# FreedomWing.net
KiCad netlist of a schematic drawn in EAGLE
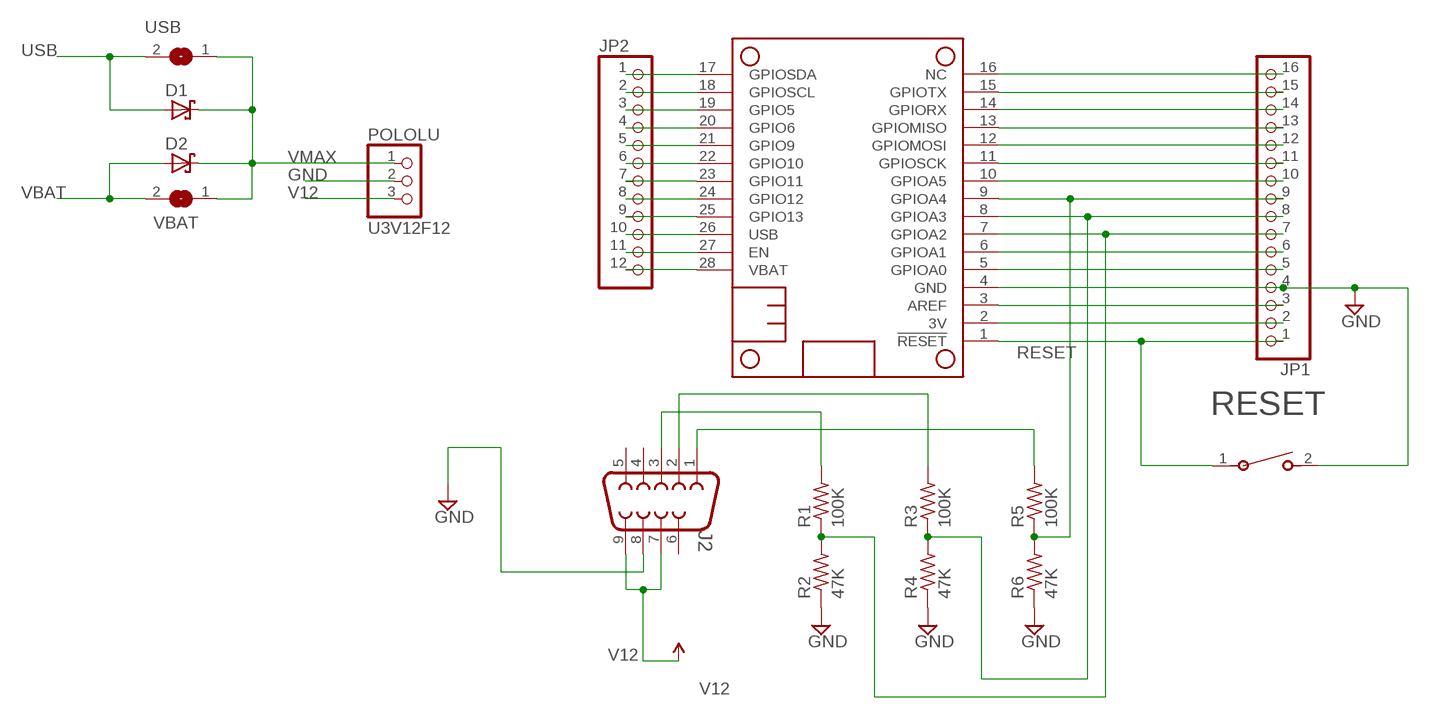
[diagram p0: schematic, sheet 1]

(export (version "E")
  (design (tool "Eeschema 10.0.6"))
  (components
    (comp (ref "D1")
      (value "SCHOTTKY-DIODEDO41-7")
      (footprint "eagle-import:DO41-7")
      (libsource (lib "eagle-import") (part "SCHOTTKY-DIODEDO41-7"))
    )
    (comp (ref "D2")
      (value "SCHOTTKY-DIODEDO41-7")
      (footprint "eagle-import:DO41-7")
      (libsource (lib "eagle-import") (part "SCHOTTKY-DIODEDO41-7"))
    )
    (comp (ref "J2")
      (value "DB9MALE")
      (footprint "eagle-import:DB9_MALE")
      (libsource (lib "eagle-import") (part "DB9MALE"))
    )
    (comp (ref "JP1")
      (value "PINHD-1X16")
      (footprint "eagle-import:1X16")
      (libsource (lib "eagle-import") (part "PINHD-1X16"))
    )
    (comp (ref "JP2")
      (value "PINHD-1X12")
      (footprint "eagle-import:1X12")
      (libsource (lib "eagle-import") (part "PINHD-1X12"))
    )
    (comp (ref "MS1")
      (value "FEATHERWING_NODIM")
      (footprint "eagle-import:FEATHERWING_DIM")
      (libsource (lib "eagle-import") (part "FEATHERWING_NODIM"))
    )
    (comp (ref "POLOLU")
      (value "U3V12F12")
      (footprint "eagle-import:1X03")
      (libsource (lib "eagle-import") (part "PINHD-1X3"))
    )
    (comp (ref "R1")
      (value "100K")
      (footprint "eagle-import:0207_10")
      (libsource (lib "eagle-import") (part "R-US_0207/10"))
    )
    (comp (ref "R2")
      (value "47K")
      (footprint "eagle-import:0207_10")
      (libsource (lib "eagle-import") (part "R-US_0207/10"))
    )
    (comp (ref "R3")
      (value "100K")
      (footprint "eagle-import:0207_10")
      (libsource (lib "eagle-import") (part "R-US_0207/10"))
    )
    (comp (ref "R4")
      (value "47K")
      (footprint "eagle-import:0207_10")
      (libsource (lib "eagle-import") (part "R-US_0207/10"))
    )
    (comp (ref "R5")
      (value "100K")
      (footprint "eagle-import:0207_10")
      (libsource (lib "eagle-import") (part "R-US_0207/10"))
    )
    (comp (ref "R6")
      (value "47K")
      (footprint "eagle-import:0207_10")
      (libsource (lib "eagle-import") (part "R-US_0207/10"))
    )
    (comp (ref "RESET")
      (value "1825966-1")
      (footprint "eagle-import:SWDIP2_256X170P100")
      (fields (field (name "COPYRIGHT") "Copyright (C) 2016 Accelerated Designs. All rights reserved"))
      (libsource (lib "eagle-import") (part "1825966-1"))
    )
    (comp (ref "USB")
      (value "SJW")
      (footprint "eagle-import:SJW")
      (libsource (lib "eagle-import") (part "SJW"))
    )
    (comp (ref "VBAT")
      (value "SJW")
      (footprint "eagle-import:SJW")
      (libsource (lib "eagle-import") (part "SJW"))
    )
  )
  (nets
    (net (code "1") (name "/RESET") (class "Default")
      (node (ref "JP1") (pin "1") (pinfunction "1_1") (pintype "passive"))
      (node (ref "MS1") (pin "1") (pinfunction "~{RESET}_1") (pintype "input"))
      (node (ref "RESET") (pin "1") (pinfunction "1_1") (pintype "passive"))
    )
    (net (code "2") (name "/USB") (class "Default")
      (node (ref "D1") (pin "A") (pinfunction "A_A") (pintype "passive"))
      (node (ref "JP2") (pin "10") (pinfunction "10_10") (pintype "passive"))
      (node (ref "MS1") (pin "26") (pinfunction "USB_26") (pintype "power_in"))
      (node (ref "USB") (pin "2") (pinfunction "2_2") (pintype "passive"))
    )
    (net (code "3") (name "/VBAT") (class "Default")
      (node (ref "D2") (pin "A") (pinfunction "A_A") (pintype "passive"))
      (node (ref "JP2") (pin "12") (pinfunction "12_12") (pintype "passive"))
      (node (ref "MS1") (pin "28") (pinfunction "VBAT_28") (pintype "power_in"))
      (node (ref "VBAT") (pin "2") (pinfunction "2_2") (pintype "passive"))
    )
    (net (code "4") (name "/VMAX") (class "Default")
      (node (ref "D1") (pin "C") (pinfunction "C_C") (pintype "passive"))
      (node (ref "D2") (pin "C") (pinfunction "C_C") (pintype "passive"))
      (node (ref "POLOLU") (pin "1") (pinfunction "1_1") (pintype "passive"))
      (node (ref "USB") (pin "1") (pinfunction "1_1") (pintype "passive"))
      (node (ref "VBAT") (pin "1") (pinfunction "1_1") (pintype "passive"))
    )
    (net (code "5") (name "GND") (class "Default")
      (node (ref "J2") (pin "8") (pinfunction "8_8") (pintype "passive"))
      (node (ref "JP1") (pin "4") (pinfunction "4_4") (pintype "passive"))
      (node (ref "MS1") (pin "4") (pinfunction "GND_4") (pintype "power_in"))
      (node (ref "POLOLU") (pin "2") (pinfunction "2_2") (pintype "passive"))
      (node (ref "R2") (pin "1") (pinfunction "1_1") (pintype "passive"))
      (node (ref "R4") (pin "1") (pinfunction "1_1") (pintype "passive"))
      (node (ref "R6") (pin "1") (pinfunction "1_1") (pintype "passive"))
      (node (ref "RESET") (pin "2") (pinfunction "2_2") (pintype "passive"))
    )
    (net (code "6") (name "Net-(J2-Pad1)") (class "Default")
      (node (ref "J2") (pin "1") (pinfunction "1_1") (pintype "passive"))
      (node (ref "R5") (pin "2") (pinfunction "2_2") (pintype "passive"))
    )
    (net (code "7") (name "Net-(J2-Pad2)") (class "Default")
      (node (ref "J2") (pin "2") (pinfunction "2_2") (pintype "passive"))
      (node (ref "R3") (pin "2") (pinfunction "2_2") (pintype "passive"))
    )
    (net (code "8") (name "Net-(J2-Pad3)") (class "Default")
      (node (ref "J2") (pin "3") (pinfunction "3_3") (pintype "passive"))
      (node (ref "R1") (pin "2") (pinfunction "2_2") (pintype "passive"))
    )
    (net (code "9") (name "Net-(MS1-3V)") (class "Default")
      (node (ref "JP1") (pin "2") (pinfunction "2_2") (pintype "passive"))
      (node (ref "MS1") (pin "2") (pinfunction "3V_2") (pintype "power_in"))
    )
    (net (code "10") (name "Net-(MS1-AREF)") (class "Default")
      (node (ref "JP1") (pin "3") (pinfunction "3_3") (pintype "passive"))
      (node (ref "MS1") (pin "3") (pinfunction "AREF_3") (pintype "passive"))
    )
    (net (code "11") (name "Net-(MS1-EN)") (class "Default")
      (node (ref "JP2") (pin "11") (pinfunction "11_11") (pintype "passive"))
      (node (ref "MS1") (pin "27") (pinfunction "EN_27") (pintype "passive"))
    )
    (net (code "12") (name "Net-(MS1-GPIO5)") (class "Default")
      (node (ref "JP2") (pin "3") (pinfunction "3_3") (pintype "passive"))
      (node (ref "MS1") (pin "19") (pinfunction "GPIO5_19") (pintype "bidirectional"))
    )
    (net (code "13") (name "Net-(MS1-GPIO6)") (class "Default")
      (node (ref "JP2") (pin "4") (pinfunction "4_4") (pintype "passive"))
      (node (ref "MS1") (pin "20") (pinfunction "GPIO6_20") (pintype "bidirectional"))
    )
    (net (code "14") (name "Net-(MS1-GPIO9)") (class "Default")
      (node (ref "JP2") (pin "5") (pinfunction "5_5") (pintype "passive"))
      (node (ref "MS1") (pin "21") (pinfunction "GPIO9_21") (pintype "bidirectional"))
    )
    (net (code "15") (name "Net-(MS1-GPIO10)") (class "Default")
      (node (ref "JP2") (pin "6") (pinfunction "6_6") (pintype "passive"))
      (node (ref "MS1") (pin "22") (pinfunction "GPIO10_22") (pintype "bidirectional"))
    )
    (net (code "16") (name "Net-(MS1-GPIO11)") (class "Default")
      (node (ref "JP2") (pin "7") (pinfunction "7_7") (pintype "passive"))
      (node (ref "MS1") (pin "23") (pinfunction "GPIO11_23") (pintype "bidirectional"))
    )
    (net (code "17") (name "Net-(MS1-GPIO12)") (class "Default")
      (node (ref "JP2") (pin "8") (pinfunction "8_8") (pintype "passive"))
      (node (ref "MS1") (pin "24") (pinfunction "GPIO12_24") (pintype "bidirectional"))
    )
    (net (code "18") (name "Net-(MS1-GPIO13)") (class "Default")
      (node (ref "JP2") (pin "9") (pinfunction "9_9") (pintype "passive"))
      (node (ref "MS1") (pin "25") (pinfunction "GPIO13_25") (pintype "bidirectional"))
    )
    (net (code "19") (name "Net-(MS1-GPIOA0)") (class "Default")
      (node (ref "JP1") (pin "5") (pinfunction "5_5") (pintype "passive"))
      (node (ref "MS1") (pin "5") (pinfunction "GPIOA0_5") (pintype "bidirectional"))
    )
    (net (code "20") (name "Net-(MS1-GPIOA1)") (class "Default")
      (node (ref "JP1") (pin "6") (pinfunction "6_6") (pintype "passive"))
      (node (ref "MS1") (pin "6") (pinfunction "GPIOA1_6") (pintype "bidirectional"))
    )
    (net (code "21") (name "Net-(MS1-GPIOA2)") (class "Default")
      (node (ref "JP1") (pin "7") (pinfunction "7_7") (pintype "passive"))
      (node (ref "MS1") (pin "7") (pinfunction "GPIOA2_7") (pintype "bidirectional"))
      (node (ref "R1") (pin "1") (pinfunction "1_1") (pintype "passive"))
      (node (ref "R2") (pin "2") (pinfunction "2_2") (pintype "passive"))
    )
    (net (code "22") (name "Net-(MS1-GPIOA3)") (class "Default")
      (node (ref "JP1") (pin "8") (pinfunction "8_8") (pintype "passive"))
      (node (ref "MS1") (pin "8") (pinfunction "GPIOA3_8") (pintype "bidirectional"))
      (node (ref "R3") (pin "1") (pinfunction "1_1") (pintype "passive"))
      (node (ref "R4") (pin "2") (pinfunction "2_2") (pintype "passive"))
    )
    (net (code "23") (name "Net-(MS1-GPIOA4)") (class "Default")
      (node (ref "JP1") (pin "9") (pinfunction "9_9") (pintype "passive"))
      (node (ref "MS1") (pin "9") (pinfunction "GPIOA4_9") (pintype "bidirectional"))
      (node (ref "R5") (pin "1") (pinfunction "1_1") (pintype "passive"))
      (node (ref "R6") (pin "2") (pinfunction "2_2") (pintype "passive"))
    )
    (net (code "24") (name "Net-(MS1-GPIOA5)") (class "Default")
      (node (ref "JP1") (pin "10") (pinfunction "10_10") (pintype "passive"))
      (node (ref "MS1") (pin "10") (pinfunction "GPIOA5_10") (pintype "bidirectional"))
    )
    (net (code "25") (name "Net-(MS1-GPIOMISO)") (class "Default")
      (node (ref "JP1") (pin "13") (pinfunction "13_13") (pintype "passive"))
      (node (ref "MS1") (pin "13") (pinfunction "GPIOMISO_13") (pintype "bidirectional"))
    )
    (net (code "26") (name "Net-(MS1-GPIOMOSI)") (class "Default")
      (node (ref "JP1") (pin "12") (pinfunction "12_12") (pintype "passive"))
      (node (ref "MS1") (pin "12") (pinfunction "GPIOMOSI_12") (pintype "bidirectional"))
    )
    (net (code "27") (name "Net-(MS1-GPIORX)") (class "Default")
      (node (ref "JP1") (pin "14") (pinfunction "14_14") (pintype "passive"))
      (node (ref "MS1") (pin "14") (pinfunction "GPIORX_14") (pintype "bidirectional"))
    )
    (net (code "28") (name "Net-(MS1-GPIOSCK)") (class "Default")
      (node (ref "JP1") (pin "11") (pinfunction "11_11") (pintype "passive"))
      (node (ref "MS1") (pin "11") (pinfunction "GPIOSCK_11") (pintype "bidirectional"))
    )
    (net (code "29") (name "Net-(MS1-GPIOSCL)") (class "Default")
      (node (ref "JP2") (pin "2") (pinfunction "2_2") (pintype "passive"))
      (node (ref "MS1") (pin "18") (pinfunction "GPIOSCL_18") (pintype "bidirectional"))
    )
    (net (code "30") (name "Net-(MS1-GPIOSDA)") (class "Default")
      (node (ref "JP2") (pin "1") (pinfunction "1_1") (pintype "passive"))
      (node (ref "MS1") (pin "17") (pinfunction "GPIOSDA_17") (pintype "bidirectional"))
    )
    (net (code "31") (name "Net-(MS1-GPIOTX)") (class "Default")
      (node (ref "JP1") (pin "15") (pinfunction "15_15") (pintype "passive"))
      (node (ref "MS1") (pin "15") (pinfunction "GPIOTX_15") (pintype "bidirectional"))
    )
    (net (code "32") (name "Net-(MS1-NC)") (class "Default")
      (node (ref "JP1") (pin "16") (pinfunction "16_16") (pintype "passive"))
      (node (ref "MS1") (pin "16") (pinfunction "NC_16") (pintype "passive"))
    )
    (net (code "33") (name "V12") (class "Default")
      (node (ref "J2") (pin "7") (pinfunction "7_7") (pintype "passive"))
      (node (ref "J2") (pin "9") (pinfunction "9_9") (pintype "passive"))
      (node (ref "POLOLU") (pin "3") (pinfunction "3_3") (pintype "passive"))
    )
    (net (code "34") (name "unconnected-(J2-Pad4)") (class "Default")
      (node (ref "J2") (pin "4") (pinfunction "4_4") (pintype "passive"))
    )
    (net (code "35") (name "unconnected-(J2-Pad5)") (class "Default")
      (node (ref "J2") (pin "5") (pinfunction "5_5") (pintype "passive"))
    )
    (net (code "36") (name "unconnected-(J2-Pad6)") (class "Default")
      (node (ref "J2") (pin "6") (pinfunction "6_6") (pintype "passive"))
    )
  )
)
